# tremolo.net
KiCad netlist of a schematic drawn in EAGLE
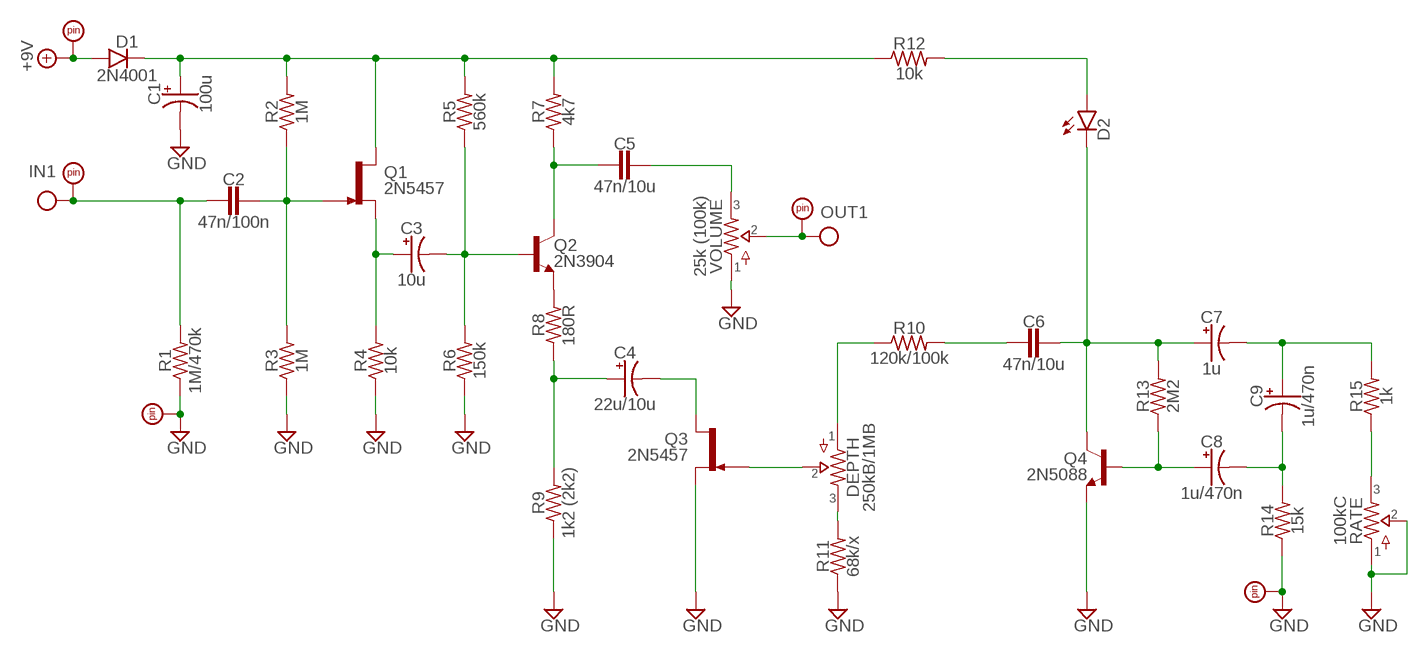
[diagram p0: schematic, sheet 1]

(export (version "E")
  (design (tool "Eeschema 10.0.6"))
  (components
    (comp (ref "C1")
      (value "100u")
      (footprint "eagle-import:050_020_1")
      (libsource (lib "eagle-import") (part "0501"))
    )
    (comp (ref "C2")
      (value "47n/100n")
      (footprint "eagle-import:BOX_SMALL")
      (libsource (lib "eagle-import") (part "CER/FILMBOX.1"))
    )
    (comp (ref "C3")
      (value "10u")
      (footprint "eagle-import:050_020_1")
      (libsource (lib "eagle-import") (part "0501"))
    )
    (comp (ref "C4")
      (value "22u/10u")
      (footprint "eagle-import:050_020_1")
      (libsource (lib "eagle-import") (part "0501"))
    )
    (comp (ref "C5")
      (value "47n/10u")
      (footprint "eagle-import:BOX_SMALL")
      (libsource (lib "eagle-import") (part "CER/FILMBOX.1"))
    )
    (comp (ref "C6")
      (value "47n/10u")
      (footprint "eagle-import:BOX_SMALL")
      (libsource (lib "eagle-import") (part "CER/FILMBOX.1"))
    )
    (comp (ref "C7")
      (value "1u")
      (footprint "eagle-import:050_020_1")
      (libsource (lib "eagle-import") (part "0501"))
    )
    (comp (ref "C8")
      (value "1u/470n")
      (footprint "eagle-import:050_020_1")
      (libsource (lib "eagle-import") (part "0501"))
    )
    (comp (ref "C9")
      (value "1u/470n")
      (footprint "eagle-import:050_020_1")
      (libsource (lib "eagle-import") (part "0501"))
    )
    (comp (ref "D1")
      (value "2N4001")
      (footprint "eagle-import:DO41-2")
      (libsource (lib "eagle-import") (part "DO41.2"))
    )
    (comp (ref "D2")
      (value "LEDA")
      (footprint "eagle-import:3MM_A")
      (libsource (lib "eagle-import") (part "LEDA"))
    )
    (comp (ref "DEPTH")
      (value "250kB/1MB")
      (footprint "eagle-import:PADS_SMALL")
      (libsource (lib "eagle-import") (part "POTSSMALL_PADS"))
    )
    (comp (ref "PAD1")
      (value "PADSQR")
      (footprint "eagle-import:SQUARE")
      (libsource (lib "eagle-import") (part "PADSQR"))
    )
    (comp (ref "PAD2")
      (value "PADSQR")
      (footprint "eagle-import:SQUARE")
      (libsource (lib "eagle-import") (part "PADSQR"))
    )
    (comp (ref "PAD3")
      (value "PADSQR")
      (footprint "eagle-import:SQUARE")
      (libsource (lib "eagle-import") (part "PADSQR"))
    )
    (comp (ref "PAD4")
      (value "PADRND")
      (footprint "eagle-import:ROUND")
      (libsource (lib "eagle-import") (part "PADRND"))
    )
    (comp (ref "PAD5")
      (value "PADRND")
      (footprint "eagle-import:ROUND")
      (libsource (lib "eagle-import") (part "PADRND"))
    )
    (comp (ref "Q1")
      (value "2N5457")
      (footprint "eagle-import:TO92-")
      (libsource (lib "eagle-import") (part "2N5457"))
    )
    (comp (ref "Q2")
      (value "2N3904")
      (footprint "eagle-import:TO92-")
      (libsource (lib "eagle-import") (part "2N3904"))
    )
    (comp (ref "Q3")
      (value "2N5457")
      (footprint "eagle-import:TO92-")
      (libsource (lib "eagle-import") (part "2N5457"))
    )
    (comp (ref "Q4")
      (value "2N5088")
      (footprint "eagle-import:TO92-")
      (libsource (lib "eagle-import") (part "2N5088"))
    )
    (comp (ref "R1")
      (value "1M/470k")
      (footprint "eagle-import:R0207_3")
      (libsource (lib "eagle-import") (part "R_.3B"))
    )
    (comp (ref "R2")
      (value "1M")
      (footprint "eagle-import:R0207_3")
      (libsource (lib "eagle-import") (part "R_.3B"))
    )
    (comp (ref "R3")
      (value "1M")
      (footprint "eagle-import:R0207_3")
      (libsource (lib "eagle-import") (part "R_.3B"))
    )
    (comp (ref "R4")
      (value "10k")
      (footprint "eagle-import:R0207_3")
      (libsource (lib "eagle-import") (part "R_.3B"))
    )
    (comp (ref "R5")
      (value "560k")
      (footprint "eagle-import:R0207_3")
      (libsource (lib "eagle-import") (part "R_.3B"))
    )
    (comp (ref "R6")
      (value "150k")
      (footprint "eagle-import:R0207_3")
      (libsource (lib "eagle-import") (part "R_.3B"))
    )
    (comp (ref "R7")
      (value "4k7")
      (footprint "eagle-import:R0207_3")
      (libsource (lib "eagle-import") (part "R_.3B"))
    )
    (comp (ref "R8")
      (value "180R")
      (footprint "eagle-import:R0207_3")
      (libsource (lib "eagle-import") (part "R_.3B"))
    )
    (comp (ref "R9")
      (value "1k2 (2k2)")
      (footprint "eagle-import:R0207_3")
      (libsource (lib "eagle-import") (part "R_.3B"))
    )
    (comp (ref "R10")
      (value "120k/100k")
      (footprint "eagle-import:R0207_3")
      (libsource (lib "eagle-import") (part "R_.3B"))
    )
    (comp (ref "R11")
      (value "68k/x")
      (footprint "eagle-import:R0207_3")
      (libsource (lib "eagle-import") (part "R_.3B"))
    )
    (comp (ref "R12")
      (value "10k")
      (footprint "eagle-import:R0207_3")
      (libsource (lib "eagle-import") (part "R_.3B"))
    )
    (comp (ref "R13")
      (value "2M2")
      (footprint "eagle-import:R0207_3")
      (libsource (lib "eagle-import") (part "R_.3B"))
    )
    (comp (ref "R14")
      (value "15k")
      (footprint "eagle-import:R0207_3")
      (libsource (lib "eagle-import") (part "R_.3B"))
    )
    (comp (ref "R15")
      (value "1k")
      (footprint "eagle-import:R0207_3")
      (libsource (lib "eagle-import") (part "R_.3B"))
    )
    (comp (ref "RATE")
      (value "100kC")
      (footprint "eagle-import:PADS_SMALL")
      (libsource (lib "eagle-import") (part "POTSSMALL_PADS"))
    )
    (comp (ref "VOLUME")
      (value "25k (100k)")
      (footprint "eagle-import:2262_TRIM")
      (libsource (lib "eagle-import") (part "POTSTRIM"))
    )
  )
  (nets
    (net (code "1") (name "+9V") (class "Default")
      (node (ref "D1") (pin "A") (pinfunction "A_A") (pintype "passive"))
      (node (ref "PAD1") (pin "1") (pinfunction "P$1_1") (pintype "bidirectional"))
    )
    (net (code "2") (name "GND") (class "Default")
      (node (ref "C1") (pin "-") (pinfunction "-_-") (pintype "passive"))
      (node (ref "PAD4") (pin "1") (pinfunction "P$1_1") (pintype "bidirectional"))
      (node (ref "PAD5") (pin "1") (pinfunction "P$1_1") (pintype "bidirectional"))
      (node (ref "Q3") (pin "2") (pinfunction "S_2") (pintype "passive"))
      (node (ref "Q4") (pin "3") (pinfunction "E_3") (pintype "passive"))
      (node (ref "R1") (pin "1") (pinfunction "1_1") (pintype "passive"))
      (node (ref "R11") (pin "1") (pinfunction "1_1") (pintype "passive"))
      (node (ref "R14") (pin "1") (pinfunction "1_1") (pintype "passive"))
      (node (ref "R3") (pin "1") (pinfunction "1_1") (pintype "passive"))
      (node (ref "R4") (pin "1") (pinfunction "1_1") (pintype "passive"))
      (node (ref "R6") (pin "1") (pinfunction "1_1") (pintype "passive"))
      (node (ref "R9") (pin "1") (pinfunction "1_1") (pintype "passive"))
      (node (ref "RATE") (pin "1") (pinfunction "1_1") (pintype "passive"))
      (node (ref "RATE") (pin "2") (pinfunction "2_2") (pintype "passive"))
      (node (ref "VOLUME") (pin "1") (pinfunction "1_1") (pintype "passive"))
    )
    (net (code "3") (name "IN") (class "Default")
      (node (ref "C2") (pin "2") (pinfunction "2_2") (pintype "passive"))
      (node (ref "PAD2") (pin "1") (pinfunction "P$1_1") (pintype "bidirectional"))
      (node (ref "R1") (pin "2") (pinfunction "2_2") (pintype "passive"))
    )
    (net (code "4") (name "Net-(C4-Pad+)") (class "Default")
      (node (ref "C4") (pin "+") (pinfunction "+_+") (pintype "passive"))
      (node (ref "R8") (pin "1") (pinfunction "1_1") (pintype "passive"))
      (node (ref "R9") (pin "2") (pinfunction "2_2") (pintype "passive"))
    )
    (net (code "5") (name "Net-(C5-Pad1)") (class "Default")
      (node (ref "C5") (pin "1") (pinfunction "1_1") (pintype "passive"))
      (node (ref "VOLUME") (pin "3") (pinfunction "3_3") (pintype "passive"))
    )
    (net (code "6") (name "Net-(C6-Pad2)") (class "Default")
      (node (ref "C6") (pin "2") (pinfunction "2_2") (pintype "passive"))
      (node (ref "R10") (pin "2") (pinfunction "2_2") (pintype "passive"))
    )
    (net (code "7") (name "Net-(C7-Pad-)") (class "Default")
      (node (ref "C7") (pin "-") (pinfunction "-_-") (pintype "passive"))
      (node (ref "C9") (pin "+") (pinfunction "+_+") (pintype "passive"))
      (node (ref "R15") (pin "2") (pinfunction "2_2") (pintype "passive"))
    )
    (net (code "8") (name "Net-(C8-Pad-)") (class "Default")
      (node (ref "C8") (pin "-") (pinfunction "-_-") (pintype "passive"))
      (node (ref "C9") (pin "-") (pinfunction "-_-") (pintype "passive"))
      (node (ref "R14") (pin "2") (pinfunction "2_2") (pintype "passive"))
    )
    (net (code "9") (name "Net-(D2-C)") (class "Default")
      (node (ref "C6") (pin "1") (pinfunction "1_1") (pintype "passive"))
      (node (ref "C7") (pin "+") (pinfunction "+_+") (pintype "passive"))
      (node (ref "D2") (pin "K") (pinfunction "C_K") (pintype "passive"))
      (node (ref "Q4") (pin "1") (pinfunction "C_1") (pintype "passive"))
      (node (ref "R13") (pin "2") (pinfunction "2_2") (pintype "passive"))
    )
    (net (code "10") (name "Net-(D2-PadA)") (class "Default")
      (node (ref "D2") (pin "A") (pinfunction "A_A") (pintype "passive"))
      (node (ref "R12") (pin "2") (pinfunction "2_2") (pintype "passive"))
    )
    (net (code "11") (name "Net-(DEPTH-Pad1)") (class "Default")
      (node (ref "DEPTH") (pin "1") (pinfunction "1_1") (pintype "passive"))
      (node (ref "R10") (pin "1") (pinfunction "1_1") (pintype "passive"))
    )
    (net (code "12") (name "Net-(DEPTH-Pad3)") (class "Default")
      (node (ref "DEPTH") (pin "3") (pinfunction "3_3") (pintype "passive"))
      (node (ref "R11") (pin "2") (pinfunction "2_2") (pintype "passive"))
    )
    (net (code "13") (name "Net-(Q1-D)") (class "Default")
      (node (ref "C1") (pin "+") (pinfunction "+_+") (pintype "passive"))
      (node (ref "D1") (pin "C") (pinfunction "C_C") (pintype "passive"))
      (node (ref "Q1") (pin "3") (pinfunction "D_3") (pintype "passive"))
      (node (ref "R12") (pin "1") (pinfunction "1_1") (pintype "passive"))
      (node (ref "R2") (pin "2") (pinfunction "2_2") (pintype "passive"))
      (node (ref "R5") (pin "2") (pinfunction "2_2") (pintype "passive"))
      (node (ref "R7") (pin "2") (pinfunction "2_2") (pintype "passive"))
    )
    (net (code "14") (name "Net-(Q1-G)") (class "Default")
      (node (ref "C2") (pin "1") (pinfunction "1_1") (pintype "passive"))
      (node (ref "Q1") (pin "1") (pinfunction "G_1") (pintype "passive"))
      (node (ref "R2") (pin "1") (pinfunction "1_1") (pintype "passive"))
      (node (ref "R3") (pin "2") (pinfunction "2_2") (pintype "passive"))
    )
    (net (code "15") (name "Net-(Q1-S)") (class "Default")
      (node (ref "C3") (pin "+") (pinfunction "+_+") (pintype "passive"))
      (node (ref "Q1") (pin "2") (pinfunction "S_2") (pintype "passive"))
      (node (ref "R4") (pin "2") (pinfunction "2_2") (pintype "passive"))
    )
    (net (code "16") (name "Net-(Q2-B)") (class "Default")
      (node (ref "C3") (pin "-") (pinfunction "-_-") (pintype "passive"))
      (node (ref "Q2") (pin "2") (pinfunction "B_2") (pintype "passive"))
      (node (ref "R5") (pin "1") (pinfunction "1_1") (pintype "passive"))
      (node (ref "R6") (pin "2") (pinfunction "2_2") (pintype "passive"))
    )
    (net (code "17") (name "Net-(Q2-C)") (class "Default")
      (node (ref "C5") (pin "2") (pinfunction "2_2") (pintype "passive"))
      (node (ref "Q2") (pin "1") (pinfunction "C_1") (pintype "passive"))
      (node (ref "R7") (pin "1") (pinfunction "1_1") (pintype "passive"))
    )
    (net (code "18") (name "Net-(Q2-E)") (class "Default")
      (node (ref "Q2") (pin "3") (pinfunction "E_3") (pintype "passive"))
      (node (ref "R8") (pin "2") (pinfunction "2_2") (pintype "passive"))
    )
    (net (code "19") (name "Net-(Q3-D)") (class "Default")
      (node (ref "C4") (pin "-") (pinfunction "-_-") (pintype "passive"))
      (node (ref "Q3") (pin "3") (pinfunction "D_3") (pintype "passive"))
    )
    (net (code "20") (name "Net-(Q3-G)") (class "Default")
      (node (ref "DEPTH") (pin "2") (pinfunction "2_2") (pintype "passive"))
      (node (ref "Q3") (pin "1") (pinfunction "G_1") (pintype "passive"))
    )
    (net (code "21") (name "Net-(Q4-B)") (class "Default")
      (node (ref "C8") (pin "+") (pinfunction "+_+") (pintype "passive"))
      (node (ref "Q4") (pin "2") (pinfunction "B_2") (pintype "passive"))
      (node (ref "R13") (pin "1") (pinfunction "1_1") (pintype "passive"))
    )
    (net (code "22") (name "Net-(R15-Pad1)") (class "Default")
      (node (ref "R15") (pin "1") (pinfunction "1_1") (pintype "passive"))
      (node (ref "RATE") (pin "3") (pinfunction "3_3") (pintype "passive"))
    )
    (net (code "23") (name "OUT") (class "Default")
      (node (ref "PAD3") (pin "1") (pinfunction "P$1_1") (pintype "bidirectional"))
      (node (ref "VOLUME") (pin "2") (pinfunction "2_2") (pintype "passive"))
    )
  )
)
